# Croduino_Damba.net
KiCad netlist of a schematic drawn in EAGLE
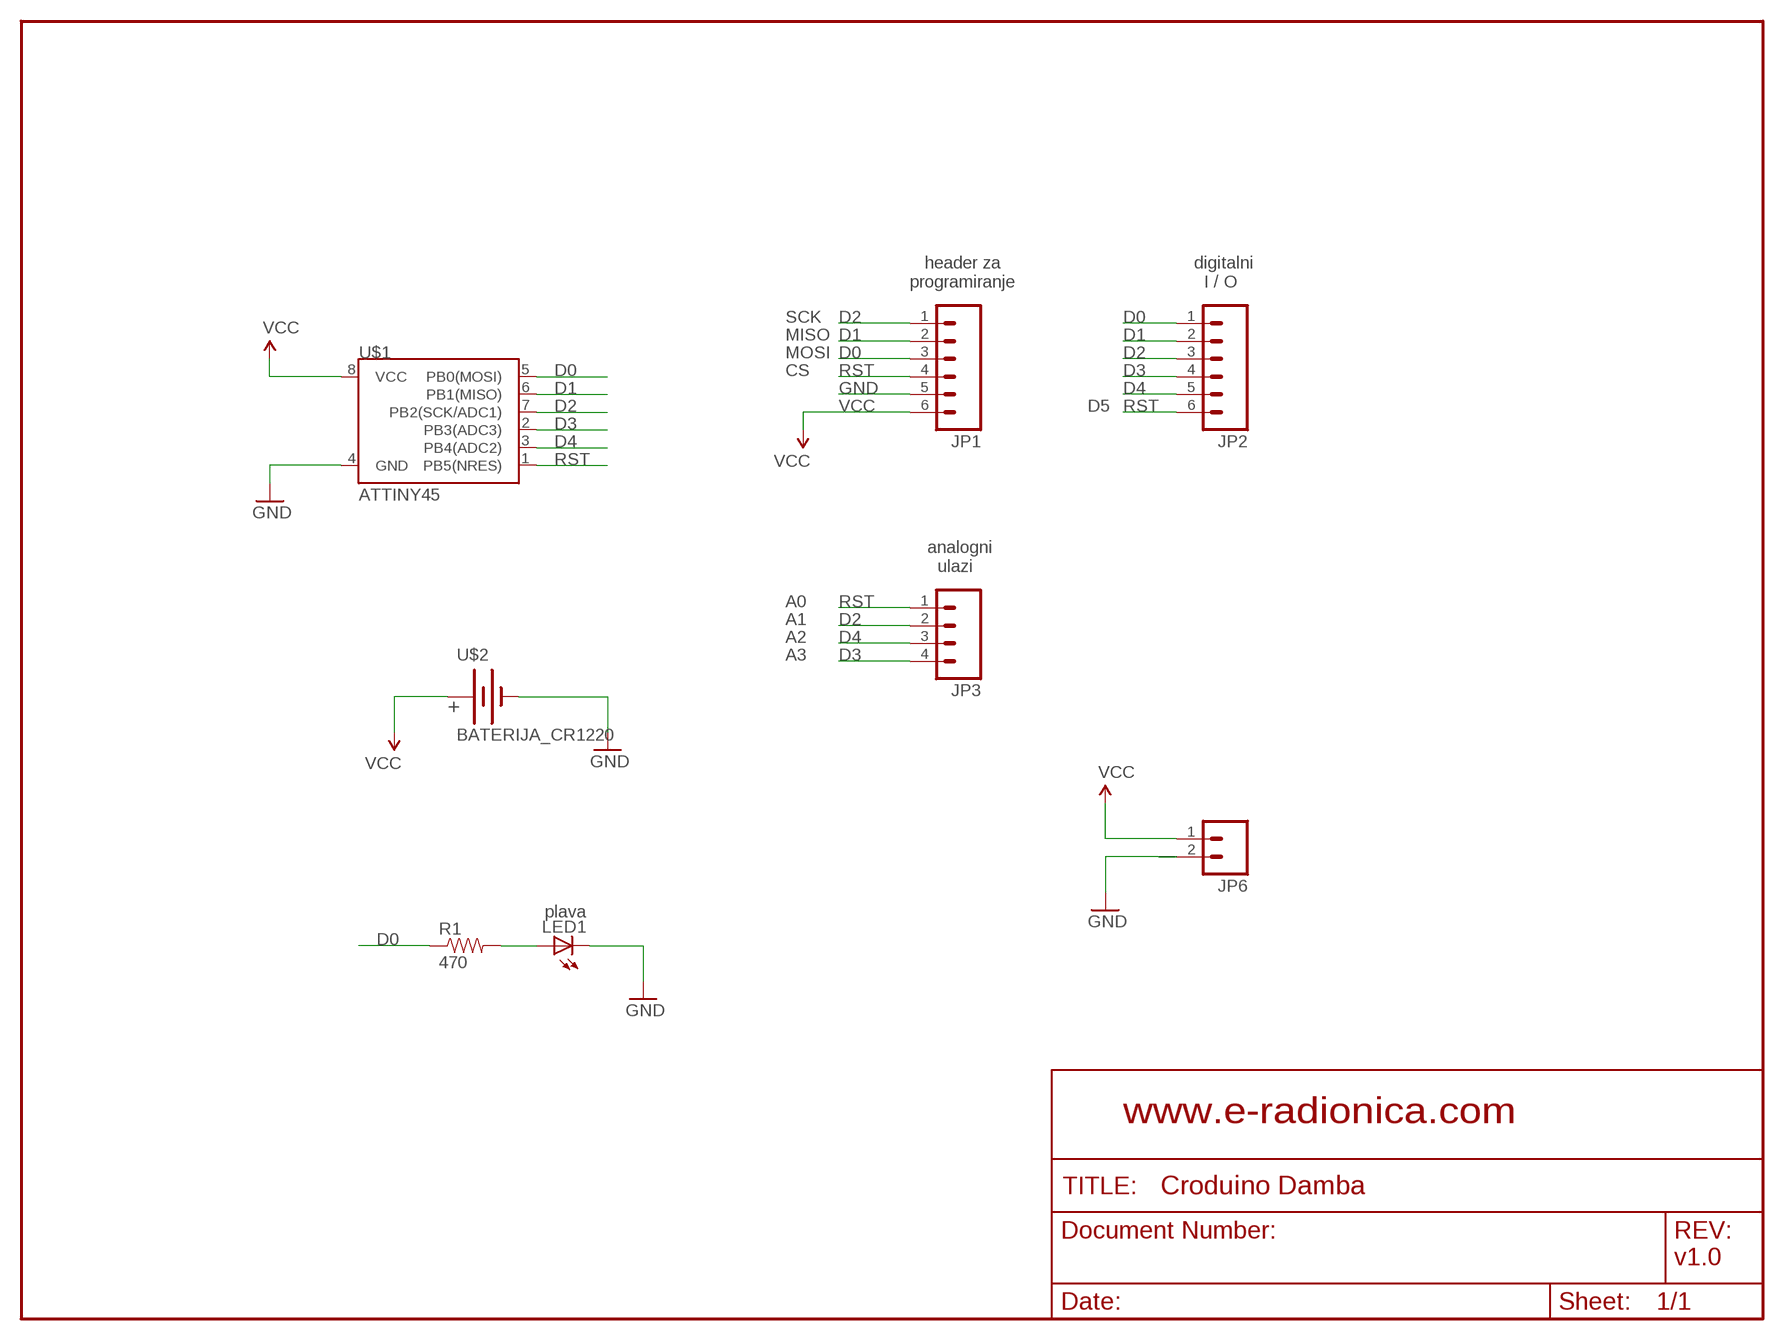
[diagram p0: schematic, sheet 1]

(export (version "E")
  (design (tool "Eeschema 10.0.6"))
  (components
    (comp (ref "JP1")
      (value "M06SIP")
      (footprint "eagle-import:1X06")
      (libsource (lib "eagle-import") (part "M06SIP"))
    )
    (comp (ref "JP2")
      (value "M06SIP")
      (footprint "eagle-import:1X06")
      (libsource (lib "eagle-import") (part "M06SIP"))
    )
    (comp (ref "JP3")
      (value "M04PTH")
      (footprint "eagle-import:1X04")
      (libsource (lib "eagle-import") (part "M04PTH"))
    )
    (comp (ref "JP6")
      (value "M02PTH")
      (footprint "eagle-import:1X02")
      (libsource (lib "eagle-import") (part "M02PTH"))
    )
    (comp (ref "LED1")
      (value "plava")
      (footprint "eagle-import:CHIPLED_0805")
      (libsource (lib "eagle-import") (part "LEDCHIPLED_0805"))
    )
    (comp (ref "R1")
      (value "470")
      (footprint "eagle-import:0603-RES")
      (libsource (lib "eagle-import") (part "RESISTOR0603-RES"))
    )
    (comp (ref "U$1")
      (value "ATTINY45")
      (footprint "eagle-import:SO08-EIAJ")
      (libsource (lib "eagle-import") (part "ATTINY45"))
    )
    (comp (ref "U$2")
      (value "BATERIJA_CR1220")
      (footprint "eagle-import:BATERIJA12MM")
      (libsource (lib "eagle-import") (part "BATERIJA_CR1220"))
    )
  )
  (nets
    (net (code "1") (name "/D0") (class "Default")
      (node (ref "JP1") (pin "3") (pinfunction "3_3") (pintype "passive"))
      (node (ref "JP2") (pin "1") (pinfunction "1_1") (pintype "passive"))
      (node (ref "R1") (pin "1") (pinfunction "1_1") (pintype "passive"))
      (node (ref "U$1") (pin "5") (pinfunction "PB0(MOSI)_5") (pintype "bidirectional"))
    )
    (net (code "2") (name "/D1") (class "Default")
      (node (ref "JP1") (pin "2") (pinfunction "2_2") (pintype "passive"))
      (node (ref "JP2") (pin "2") (pinfunction "2_2") (pintype "passive"))
      (node (ref "U$1") (pin "6") (pinfunction "PB1(MISO)_6") (pintype "bidirectional"))
    )
    (net (code "3") (name "/D2") (class "Default")
      (node (ref "JP1") (pin "1") (pinfunction "1_1") (pintype "passive"))
      (node (ref "JP2") (pin "3") (pinfunction "3_3") (pintype "passive"))
      (node (ref "JP3") (pin "2") (pinfunction "2_2") (pintype "passive"))
      (node (ref "U$1") (pin "7") (pinfunction "PB2(SCK/ADC1)_7") (pintype "bidirectional"))
    )
    (net (code "4") (name "/D3") (class "Default")
      (node (ref "JP2") (pin "4") (pinfunction "4_4") (pintype "passive"))
      (node (ref "JP3") (pin "4") (pinfunction "4_4") (pintype "passive"))
      (node (ref "U$1") (pin "2") (pinfunction "PB3(ADC3)_2") (pintype "bidirectional"))
    )
    (net (code "5") (name "/D4") (class "Default")
      (node (ref "JP2") (pin "5") (pinfunction "5_5") (pintype "passive"))
      (node (ref "JP3") (pin "3") (pinfunction "3_3") (pintype "passive"))
      (node (ref "U$1") (pin "3") (pinfunction "PB4(ADC2)_3") (pintype "bidirectional"))
    )
    (net (code "6") (name "/RST") (class "Default")
      (node (ref "JP1") (pin "4") (pinfunction "4_4") (pintype "passive"))
      (node (ref "JP2") (pin "6") (pinfunction "6_6") (pintype "passive"))
      (node (ref "JP3") (pin "1") (pinfunction "1_1") (pintype "passive"))
      (node (ref "U$1") (pin "1") (pinfunction "PB5(NRES)_1") (pintype "bidirectional"))
    )
    (net (code "7") (name "GND") (class "Default")
      (node (ref "JP1") (pin "5") (pinfunction "5_5") (pintype "passive"))
      (node (ref "JP6") (pin "2") (pinfunction "2_2") (pintype "passive"))
      (node (ref "LED1") (pin "C") (pinfunction "C_C") (pintype "passive"))
      (node (ref "U$1") (pin "4") (pinfunction "GND_4") (pintype "bidirectional"))
      (node (ref "U$2") (pin "-") (pinfunction "-_-") (pintype "power_in"))
    )
    (net (code "8") (name "Net-(LED1-PadA)") (class "Default")
      (node (ref "LED1") (pin "A") (pinfunction "A_A") (pintype "passive"))
      (node (ref "R1") (pin "2") (pinfunction "2_2") (pintype "passive"))
    )
    (net (code "9") (name "VCC") (class "Default")
      (node (ref "JP1") (pin "6") (pinfunction "6_6") (pintype "passive"))
      (node (ref "JP6") (pin "1") (pinfunction "1_1") (pintype "passive"))
      (node (ref "U$1") (pin "8") (pinfunction "VCC_8") (pintype "bidirectional"))
      (node (ref "U$2") (pin "+") (pinfunction "+_+") (pintype "power_in"))
    )
  )
)
